# rx_mod.net
KiCad netlist of a schematic drawn in EAGLE
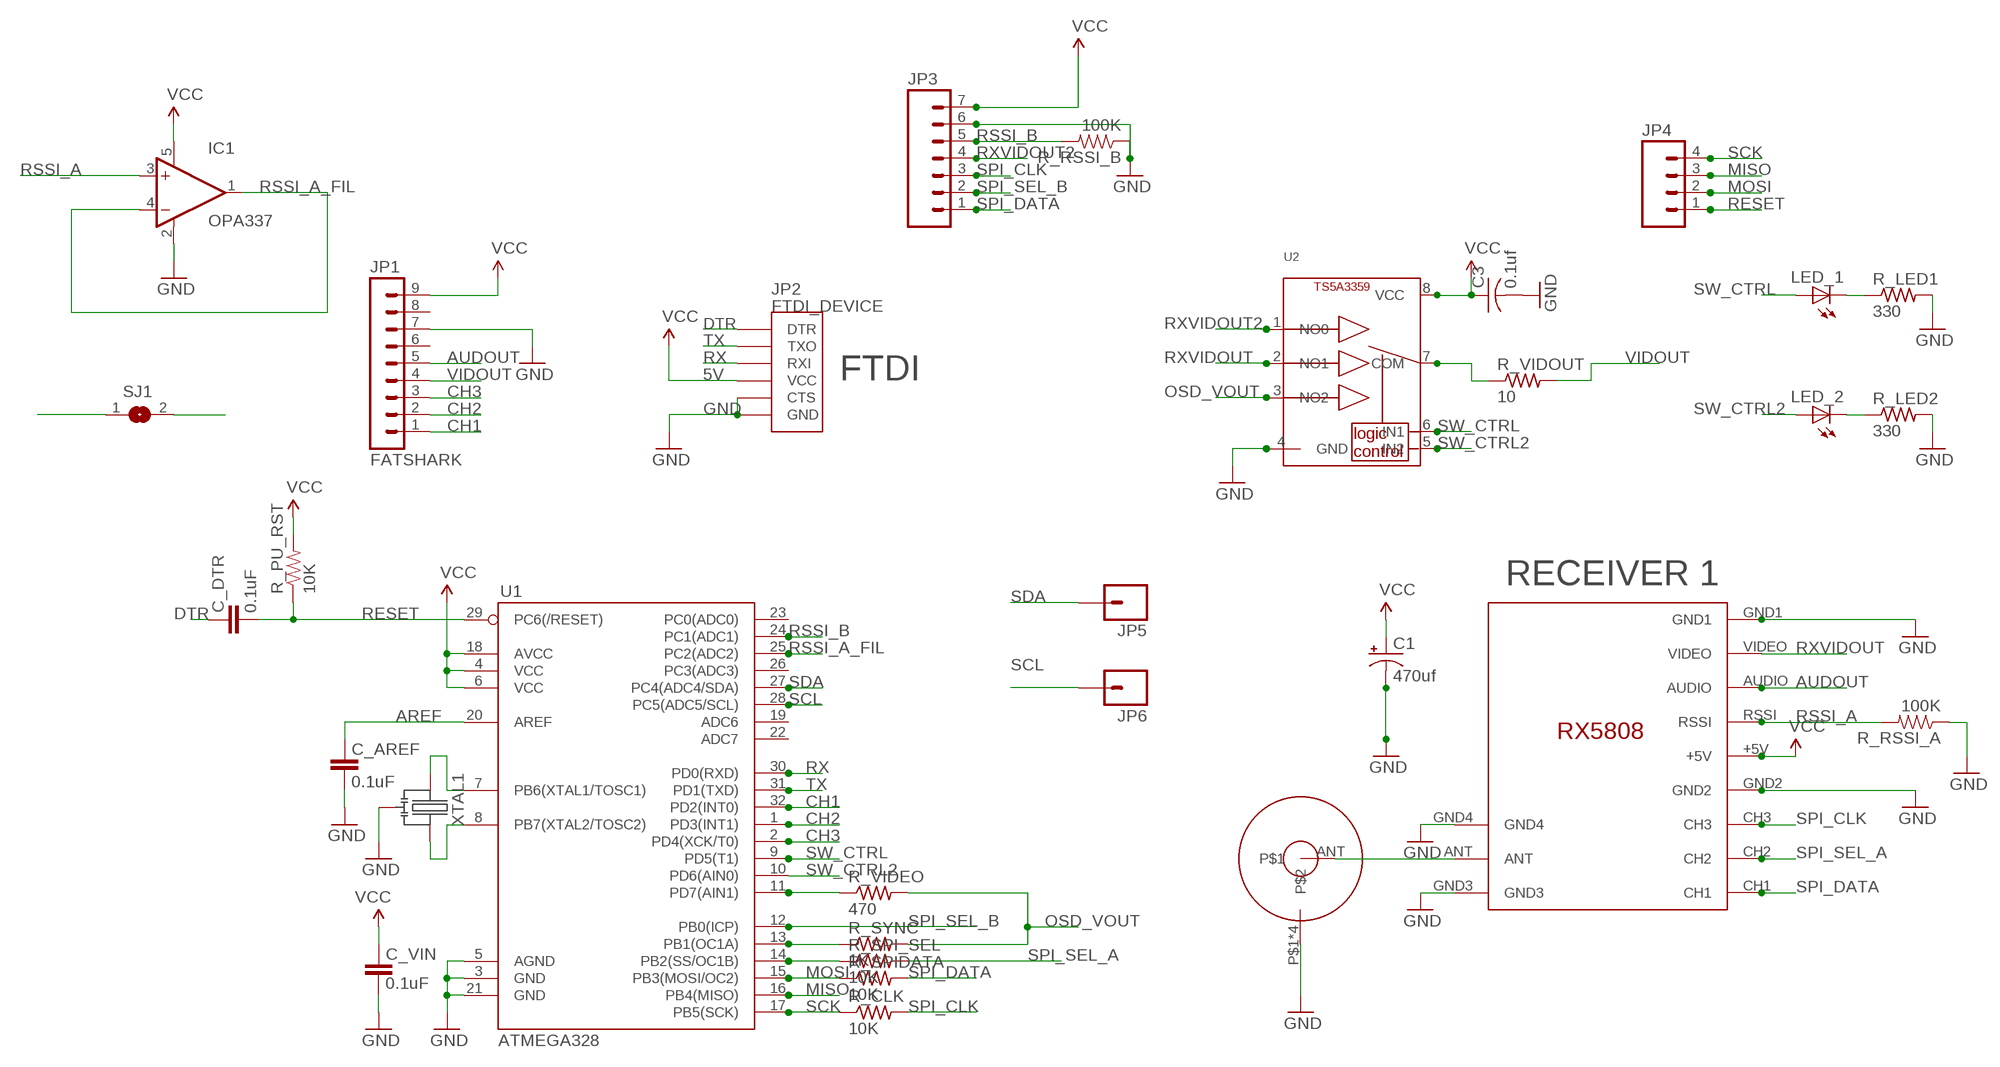
[diagram p0: schematic, sheet 1]

(export (version "E")
  (design (tool "Eeschema 10.0.6"))
  (components
    (comp (ref "C1")
      (value "470uf")
      (footprint "eagle-import:EIA7343")
      (libsource (lib "eagle-import") (part "CAP_POL7343"))
    )
    (comp (ref "C3")
      (value "0.1uf")
      (footprint "eagle-import:C0603")
      (libsource (lib "eagle-import") (part "C-USC0603"))
    )
    (comp (ref "C_AREF")
      (value "0.1uF")
      (footprint "eagle-import:0603-CAP")
      (libsource (lib "eagle-import") (part "CAP0603-CAP"))
    )
    (comp (ref "C_DTR")
      (value "0.1uF")
      (footprint "eagle-import:0603-CAP")
      (libsource (lib "eagle-import") (part "CAP0603-CAP"))
    )
    (comp (ref "C_VIN")
      (value "0.1uF")
      (footprint "eagle-import:0603-CAP")
      (libsource (lib "eagle-import") (part "CAP0603-CAP"))
    )
    (comp (ref "IC1")
      (value "OPA336N")
      (footprint "eagle-import:SOT23-5")
      (fields (field (name "MPN") "OPA336NA"))
      (libsource (lib "eagle-import") (part "OPA336N"))
    )
    (comp (ref "JP1")
      (value "FATSHARK")
      (footprint "eagle-import:MA09-1")
      (libsource (lib "eagle-import") (part "MA09-1"))
    )
    (comp (ref "JP2")
      (value "FTDI_DEVICE")
      (footprint "eagle-import:FTDI_DEVICE_SIDE")
      (libsource (lib "eagle-import") (part "FTDI_DEVICE"))
    )
    (comp (ref "JP3")
      (value "M07")
      (footprint "eagle-import:1X07")
      (libsource (lib "eagle-import") (part "M07"))
    )
    (comp (ref "JP4")
      (value "M04PTH")
      (footprint "eagle-import:1X04")
      (libsource (lib "eagle-import") (part "M04PTH"))
    )
    (comp (ref "JP5")
      (value "M01SMD-4.5X1.5")
      (footprint "eagle-import:PAD-1.5X4.5")
      (libsource (lib "eagle-import") (part "M01SMD-4.5X1.5"))
    )
    (comp (ref "JP6")
      (value "M01SMD-4.5X1.5")
      (footprint "eagle-import:PAD-1.5X4.5")
      (libsource (lib "eagle-import") (part "M01SMD-4.5X1.5"))
    )
    (comp (ref "LED_1")
      (value "LEDSML0603")
      (footprint "eagle-import:SML0603")
      (libsource (lib "eagle-import") (part "LEDSML0603"))
    )
    (comp (ref "LED_2")
      (value "LEDSML0603")
      (footprint "eagle-import:SML0603")
      (libsource (lib "eagle-import") (part "LEDSML0603"))
    )
    (comp (ref "RECEIVER_A")
      (value "RX5808_A")
      (footprint "eagle-import:RX5808")
      (libsource (lib "eagle-import") (part "RX5808"))
    )
    (comp (ref "R_CLK")
      (value "10K")
      (footprint "eagle-import:R0805")
      (libsource (lib "eagle-import") (part "R-US_R0805"))
    )
    (comp (ref "R_LED1")
      (value "330")
      (footprint "eagle-import:R0603")
      (libsource (lib "eagle-import") (part "R-US_R0603"))
    )
    (comp (ref "R_LED2")
      (value "330")
      (footprint "eagle-import:R0603")
      (libsource (lib "eagle-import") (part "R-US_R0603"))
    )
    (comp (ref "R_PU_RST")
      (value "10K")
      (footprint "eagle-import:0603-RES")
      (libsource (lib "eagle-import") (part "RESISTOR0603-RES"))
    )
    (comp (ref "R_RSSI_A")
      (value "100K")
      (footprint "eagle-import:0603-RES")
      (libsource (lib "eagle-import") (part "RESISTOR0603-RES"))
    )
    (comp (ref "R_RSSI_B")
      (value "100K")
      (footprint "eagle-import:0603-RES")
      (libsource (lib "eagle-import") (part "RESISTOR0603-RES"))
    )
    (comp (ref "R_SPIDATA")
      (value "10K")
      (footprint "eagle-import:R0805")
      (libsource (lib "eagle-import") (part "R-US_R0805"))
    )
    (comp (ref "R_SPI_SEL")
      (value "10K")
      (footprint "eagle-import:R0805")
      (libsource (lib "eagle-import") (part "R-US_R0805"))
    )
    (comp (ref "R_SYNC")
      (value "1K")
      (footprint "eagle-import:R0805")
      (libsource (lib "eagle-import") (part "R-US_R0805"))
    )
    (comp (ref "R_VIDEO")
      (value "470")
      (footprint "eagle-import:R0805")
      (libsource (lib "eagle-import") (part "R-US_R0805"))
    )
    (comp (ref "R_VIDOUT")
      (value "10")
      (footprint "eagle-import:R0805")
      (libsource (lib "eagle-import") (part "R-US_R0805"))
    )
    (comp (ref "SJ1") (value "SJ") (footprint "eagle-import:SJ") (libsource (lib "eagle-import") (part "SJ")))
    (comp (ref "U$1")
      (value "SMA_ANTENNA")
      (footprint "eagle-import:SMA_CONNECTOR")
      (libsource (lib "eagle-import") (part "SMA_ANTENNA"))
    )
    (comp (ref "U1")
      (value "ATMEGA328")
      (footprint "eagle-import:TQFP32-08")
      (libsource (lib "eagle-import") (part "ATMEGA168"))
    )
    (comp (ref "U2")
      (value "TS5A3359")
      (footprint "eagle-import:VFSOP-8")
      (libsource (lib "eagle-import") (part "TS5A3359"))
    )
    (comp (ref "XTAL1")
      (value "CSTCE16M0V53-R0")
      (footprint "eagle-import:CSTCE16M0V53-R0")
      (libsource (lib "eagle-import") (part "CSTCE16M0V53-R0"))
    )
  )
  (nets
    (net (code "1") (name "/AREF") (class "Default")
      (node (ref "C_AREF") (pin "2") (pinfunction "2_2") (pintype "passive"))
      (node (ref "U1") (pin "20") (pinfunction "AREF_20") (pintype "bidirectional"))
    )
    (net (code "2") (name "/AUDOUT") (class "Default")
      (node (ref "JP1") (pin "5") (pinfunction "5_5") (pintype "passive"))
      (node (ref "RECEIVER_A") (pin "AUDIO") (pinfunction "AUDIO_AUDIO") (pintype "bidirectional"))
    )
    (net (code "3") (name "/CH1") (class "Default")
      (node (ref "JP1") (pin "1") (pinfunction "1_1") (pintype "passive"))
      (node (ref "U1") (pin "32") (pinfunction "PD2(INT0)_32") (pintype "bidirectional"))
    )
    (net (code "4") (name "/CH2") (class "Default")
      (node (ref "JP1") (pin "2") (pinfunction "2_2") (pintype "passive"))
      (node (ref "U1") (pin "1") (pinfunction "PD3(INT1)_1") (pintype "bidirectional"))
    )
    (net (code "5") (name "/CH3") (class "Default")
      (node (ref "JP1") (pin "3") (pinfunction "3_3") (pintype "passive"))
      (node (ref "U1") (pin "2") (pinfunction "PD4(XCK/T0)_2") (pintype "bidirectional"))
    )
    (net (code "6") (name "/DTR") (class "Default")
      (node (ref "C_DTR") (pin "2") (pinfunction "2_2") (pintype "passive"))
      (node (ref "JP2") (pin "P$1") (pinfunction "DTR_P$1") (pintype "bidirectional"))
    )
    (net (code "7") (name "/MISO") (class "Default")
      (node (ref "JP4") (pin "3") (pinfunction "3_3") (pintype "passive"))
      (node (ref "U1") (pin "16") (pinfunction "PB4(MISO)_16") (pintype "bidirectional"))
    )
    (net (code "8") (name "/MOSI") (class "Default")
      (node (ref "JP4") (pin "2") (pinfunction "2_2") (pintype "passive"))
      (node (ref "R_SPIDATA") (pin "1") (pinfunction "1_1") (pintype "passive"))
      (node (ref "U1") (pin "15") (pinfunction "PB3(MOSI/OC2)_15") (pintype "bidirectional"))
    )
    (net (code "9") (name "/OSD_VOUT") (class "Default")
      (node (ref "R_SYNC") (pin "2") (pinfunction "2_2") (pintype "passive"))
      (node (ref "R_VIDEO") (pin "2") (pinfunction "2_2") (pintype "passive"))
      (node (ref "U2") (pin "3") (pinfunction "NO2_3") (pintype "input"))
    )
    (net (code "10") (name "/RESET") (class "Default")
      (node (ref "C_DTR") (pin "1") (pinfunction "1_1") (pintype "passive"))
      (node (ref "JP4") (pin "1") (pinfunction "1_1") (pintype "passive"))
      (node (ref "R_PU_RST") (pin "1") (pinfunction "1_1") (pintype "passive"))
      (node (ref "U1") (pin "29") (pinfunction "PC6(/RESET)_29") (pintype "bidirectional"))
    )
    (net (code "11") (name "/RSSI_A") (class "Default")
      (node (ref "IC1") (pin "3") (pinfunction "+IN_3") (pintype "input"))
      (node (ref "RECEIVER_A") (pin "RSSI") (pinfunction "RSSI_RSSI") (pintype "bidirectional"))
      (node (ref "R_RSSI_A") (pin "2") (pinfunction "2_2") (pintype "passive"))
      (node (ref "SJ1") (pin "1") (pinfunction "1_1") (pintype "passive"))
    )
    (net (code "12") (name "/RSSI_A_FIL") (class "Default")
      (node (ref "IC1") (pin "1") (pinfunction "OUT_1") (pintype "output"))
      (node (ref "IC1") (pin "4") (pinfunction "-IN_4") (pintype "input"))
      (node (ref "SJ1") (pin "2") (pinfunction "2_2") (pintype "passive"))
      (node (ref "U1") (pin "25") (pinfunction "PC2(ADC2)_25") (pintype "bidirectional"))
    )
    (net (code "13") (name "/RSSI_B") (class "Default")
      (node (ref "JP3") (pin "5") (pinfunction "5_5") (pintype "passive"))
      (node (ref "R_RSSI_B") (pin "2") (pinfunction "2_2") (pintype "passive"))
      (node (ref "U1") (pin "24") (pinfunction "PC1(ADC1)_24") (pintype "bidirectional"))
    )
    (net (code "14") (name "/RX") (class "Default")
      (node (ref "JP2") (pin "P$3") (pinfunction "RXI_P$3") (pintype "bidirectional"))
      (node (ref "U1") (pin "30") (pinfunction "PD0(RXD)_30") (pintype "bidirectional"))
    )
    (net (code "15") (name "/RXVIDOUT") (class "Default")
      (node (ref "RECEIVER_A") (pin "VIDEO") (pinfunction "VIDEO_VIDEO") (pintype "bidirectional"))
      (node (ref "U2") (pin "2") (pinfunction "NO1_2") (pintype "input"))
    )
    (net (code "16") (name "/RXVIDOUT2") (class "Default")
      (node (ref "JP3") (pin "4") (pinfunction "4_4") (pintype "passive"))
      (node (ref "U2") (pin "1") (pinfunction "NO0_1") (pintype "input"))
    )
    (net (code "17") (name "/SCK") (class "Default")
      (node (ref "JP4") (pin "4") (pinfunction "4_4") (pintype "passive"))
      (node (ref "R_CLK") (pin "1") (pinfunction "1_1") (pintype "passive"))
      (node (ref "U1") (pin "17") (pinfunction "PB5(SCK)_17") (pintype "bidirectional"))
    )
    (net (code "18") (name "/SCL") (class "Default")
      (node (ref "JP6") (pin "P$1") (pinfunction "1_P$1") (pintype "passive"))
      (node (ref "U1") (pin "28") (pinfunction "PC5(ADC5/SCL)_28") (pintype "bidirectional"))
    )
    (net (code "19") (name "/SDA") (class "Default")
      (node (ref "JP5") (pin "P$1") (pinfunction "1_P$1") (pintype "passive"))
      (node (ref "U1") (pin "27") (pinfunction "PC4(ADC4/SDA)_27") (pintype "bidirectional"))
    )
    (net (code "20") (name "/SPI_CLK") (class "Default")
      (node (ref "JP3") (pin "3") (pinfunction "3_3") (pintype "passive"))
      (node (ref "RECEIVER_A") (pin "CH3") (pinfunction "CH3_CH3") (pintype "bidirectional"))
      (node (ref "R_CLK") (pin "2") (pinfunction "2_2") (pintype "passive"))
    )
    (net (code "21") (name "/SPI_DATA") (class "Default")
      (node (ref "JP3") (pin "1") (pinfunction "1_1") (pintype "passive"))
      (node (ref "RECEIVER_A") (pin "CH1") (pinfunction "CH1_CH1") (pintype "bidirectional"))
      (node (ref "R_SPIDATA") (pin "2") (pinfunction "2_2") (pintype "passive"))
    )
    (net (code "22") (name "/SPI_SEL_A") (class "Default")
      (node (ref "RECEIVER_A") (pin "CH2") (pinfunction "CH2_CH2") (pintype "bidirectional"))
      (node (ref "R_SPI_SEL") (pin "2") (pinfunction "2_2") (pintype "passive"))
    )
    (net (code "23") (name "/SPI_SEL_B") (class "Default")
      (node (ref "JP3") (pin "2") (pinfunction "2_2") (pintype "passive"))
      (node (ref "U1") (pin "12") (pinfunction "PB0(ICP)_12") (pintype "bidirectional"))
    )
    (net (code "24") (name "/SW_CTRL") (class "Default")
      (node (ref "LED_1") (pin "A") (pinfunction "A_A") (pintype "passive"))
      (node (ref "U1") (pin "9") (pinfunction "PD5(T1)_9") (pintype "bidirectional"))
      (node (ref "U2") (pin "6") (pinfunction "IN1_6") (pintype "output"))
    )
    (net (code "25") (name "/SW_CTRL2") (class "Default")
      (node (ref "LED_2") (pin "A") (pinfunction "A_A") (pintype "passive"))
      (node (ref "U1") (pin "10") (pinfunction "PD6(AIN0)_10") (pintype "bidirectional"))
      (node (ref "U2") (pin "5") (pinfunction "IN2_5") (pintype "output"))
    )
    (net (code "26") (name "/TX") (class "Default")
      (node (ref "JP2") (pin "P$2") (pinfunction "TXO_P$2") (pintype "bidirectional"))
      (node (ref "U1") (pin "31") (pinfunction "PD1(TXD)_31") (pintype "bidirectional"))
    )
    (net (code "27") (name "/VIDOUT") (class "Default")
      (node (ref "JP1") (pin "4") (pinfunction "4_4") (pintype "passive"))
      (node (ref "R_VIDOUT") (pin "2") (pinfunction "2_2") (pintype "passive"))
    )
    (net (code "28") (name "GND") (class "Default")
      (node (ref "C1") (pin "C") (pinfunction "-_C") (pintype "passive"))
      (node (ref "C3") (pin "2") (pinfunction "2_2") (pintype "passive"))
      (node (ref "C_AREF") (pin "1") (pinfunction "1_1") (pintype "passive"))
      (node (ref "C_VIN") (pin "1") (pinfunction "1_1") (pintype "passive"))
      (node (ref "IC1") (pin "2") (pinfunction "V-_2") (pintype "power_in"))
      (node (ref "JP1") (pin "7") (pinfunction "7_7") (pintype "passive"))
      (node (ref "JP2") (pin "P$5") (pinfunction "CTS_P$5") (pintype "bidirectional"))
      (node (ref "JP2") (pin "P$6") (pinfunction "GND_P$6") (pintype "bidirectional"))
      (node (ref "JP3") (pin "6") (pinfunction "6_6") (pintype "passive"))
      (node (ref "RECEIVER_A") (pin "GND1") (pinfunction "GND1_GND1") (pintype "bidirectional"))
      (node (ref "RECEIVER_A") (pin "GND2") (pinfunction "GND2_GND2") (pintype "bidirectional"))
      (node (ref "RECEIVER_A") (pin "GND3") (pinfunction "GND3_GND3") (pintype "bidirectional"))
      (node (ref "RECEIVER_A") (pin "GND4") (pinfunction "GND4_GND4") (pintype "bidirectional"))
      (node (ref "R_LED1") (pin "2") (pinfunction "2_2") (pintype "passive"))
      (node (ref "R_LED2") (pin "2") (pinfunction "2_2") (pintype "passive"))
      (node (ref "R_RSSI_A") (pin "1") (pinfunction "1_1") (pintype "passive"))
      (node (ref "R_RSSI_B") (pin "1") (pinfunction "1_1") (pintype "passive"))
      (node (ref "U$1") (pin "P$1") (pinfunction "P$2_P$1") (pintype "bidirectional"))
      (node (ref "U$1") (pin "P$2") (pinfunction "P$2_P$2") (pintype "bidirectional"))
      (node (ref "U$1") (pin "P$3") (pinfunction "P$2_P$3") (pintype "bidirectional"))
      (node (ref "U$1") (pin "P$4") (pinfunction "P$2_P$4") (pintype "bidirectional"))
      (node (ref "U1") (pin "21") (pinfunction "GND_21") (pintype "bidirectional"))
      (node (ref "U1") (pin "3") (pinfunction "GND_3") (pintype "bidirectional"))
      (node (ref "U1") (pin "5") (pinfunction "AGND_5") (pintype "bidirectional"))
      (node (ref "U2") (pin "4") (pinfunction "GND_4") (pintype "power_in"))
      (node (ref "XTAL1") (pin "2") (pinfunction "2_2") (pintype "bidirectional"))
    )
    (net (code "29") (name "Net-(LED_1-PadC)") (class "Default")
      (node (ref "LED_1") (pin "C") (pinfunction "C_C") (pintype "passive"))
      (node (ref "R_LED1") (pin "1") (pinfunction "1_1") (pintype "passive"))
    )
    (net (code "30") (name "Net-(LED_2-PadC)") (class "Default")
      (node (ref "LED_2") (pin "C") (pinfunction "C_C") (pintype "passive"))
      (node (ref "R_LED2") (pin "1") (pinfunction "1_1") (pintype "passive"))
    )
    (net (code "31") (name "Net-(U$1-P$1)") (class "Default")
      (node (ref "RECEIVER_A") (pin "ANT") (pinfunction "ANT_ANT") (pintype "bidirectional"))
      (node (ref "U$1") (pin "ANT") (pinfunction "P$1_ANT") (pintype "bidirectional"))
    )
    (net (code "32") (name "Net-(U1-PB1(OC1A))") (class "Default")
      (node (ref "R_SYNC") (pin "1") (pinfunction "1_1") (pintype "passive"))
      (node (ref "U1") (pin "13") (pinfunction "PB1(OC1A)_13") (pintype "bidirectional"))
    )
    (net (code "33") (name "Net-(U1-PB2(SS{slash}OC1B))") (class "Default")
      (node (ref "R_SPI_SEL") (pin "1") (pinfunction "1_1") (pintype "passive"))
      (node (ref "U1") (pin "14") (pinfunction "PB2(SS/OC1B)_14") (pintype "bidirectional"))
    )
    (net (code "34") (name "Net-(U1-PB6(XTAL1{slash}TOSC1))") (class "Default")
      (node (ref "U1") (pin "7") (pinfunction "PB6(XTAL1/TOSC1)_7") (pintype "bidirectional"))
      (node (ref "XTAL1") (pin "1") (pinfunction "1_1") (pintype "bidirectional"))
    )
    (net (code "35") (name "Net-(U1-PB7(XTAL2{slash}TOSC2))") (class "Default")
      (node (ref "U1") (pin "8") (pinfunction "PB7(XTAL2/TOSC2)_8") (pintype "bidirectional"))
      (node (ref "XTAL1") (pin "3") (pinfunction "3_3") (pintype "bidirectional"))
    )
    (net (code "36") (name "Net-(U1-PD7(AIN1))") (class "Default")
      (node (ref "R_VIDEO") (pin "1") (pinfunction "1_1") (pintype "passive"))
      (node (ref "U1") (pin "11") (pinfunction "PD7(AIN1)_11") (pintype "bidirectional"))
    )
    (net (code "37") (name "Net-(U2-COM)") (class "Default")
      (node (ref "R_VIDOUT") (pin "1") (pinfunction "1_1") (pintype "passive"))
      (node (ref "U2") (pin "7") (pinfunction "COM_7") (pintype "input"))
    )
    (net (code "38") (name "VCC") (class "Default")
      (node (ref "C1") (pin "A") (pinfunction "+_A") (pintype "passive"))
      (node (ref "C3") (pin "1") (pinfunction "1_1") (pintype "passive"))
      (node (ref "C_VIN") (pin "2") (pinfunction "2_2") (pintype "passive"))
      (node (ref "IC1") (pin "5") (pinfunction "V+_5") (pintype "power_in"))
      (node (ref "JP1") (pin "9") (pinfunction "9_9") (pintype "passive"))
      (node (ref "JP2") (pin "P$4") (pinfunction "VCC_P$4") (pintype "bidirectional"))
      (node (ref "JP3") (pin "7") (pinfunction "7_7") (pintype "passive"))
      (node (ref "RECEIVER_A") (pin "+5V") (pinfunction "+5V_+5V") (pintype "bidirectional"))
      (node (ref "R_PU_RST") (pin "2") (pinfunction "2_2") (pintype "passive"))
      (node (ref "U1") (pin "18") (pinfunction "AVCC_18") (pintype "bidirectional"))
      (node (ref "U1") (pin "4") (pinfunction "VCC_4") (pintype "bidirectional"))
      (node (ref "U1") (pin "6") (pinfunction "VCC_6") (pintype "bidirectional"))
      (node (ref "U2") (pin "8") (pinfunction "VCC_8") (pintype "power_in"))
    )
    (net (code "39") (name "unconnected-(JP1-Pad6)") (class "Default")
      (node (ref "JP1") (pin "6") (pinfunction "6_6") (pintype "passive"))
    )
    (net (code "40") (name "unconnected-(JP1-Pad8)") (class "Default")
      (node (ref "JP1") (pin "8") (pinfunction "8_8") (pintype "passive"))
    )
    (net (code "41") (name "unconnected-(U1-ADC6-Pad19)") (class "Default")
      (node (ref "U1") (pin "19") (pinfunction "ADC6_19") (pintype "bidirectional"))
    )
    (net (code "42") (name "unconnected-(U1-ADC7-Pad22)") (class "Default")
      (node (ref "U1") (pin "22") (pinfunction "ADC7_22") (pintype "bidirectional"))
    )
    (net (code "43") (name "unconnected-(U1-PC0(ADC0)-Pad23)") (class "Default")
      (node (ref "U1") (pin "23") (pinfunction "PC0(ADC0)_23") (pintype "bidirectional"))
    )
    (net (code "44") (name "unconnected-(U1-PC3(ADC3)-Pad26)") (class "Default")
      (node (ref "U1") (pin "26") (pinfunction "PC3(ADC3)_26") (pintype "bidirectional"))
    )
  )
)
